# PowerDetector.net
KiCad netlist of a schematic drawn in Altium Designer
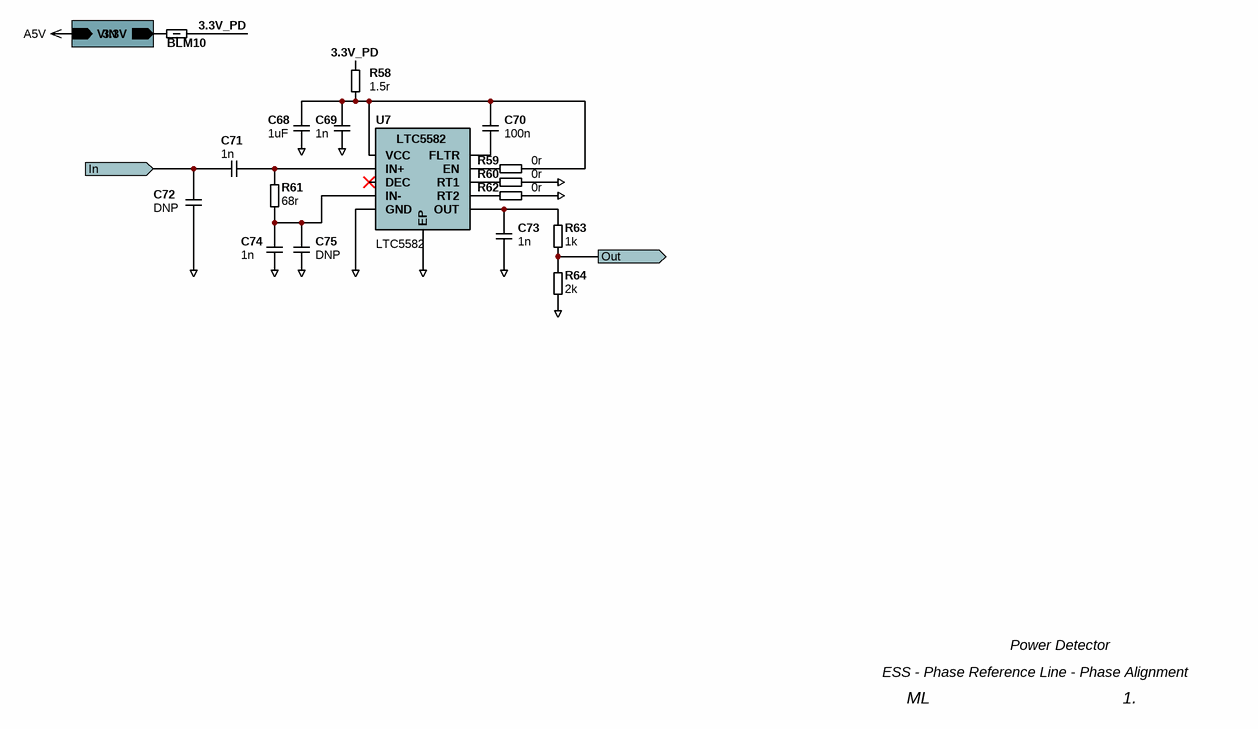
[diagram p0: PowerDetector.SchDoc]

(export (version "E")
  (design (tool "Eeschema 10.0.6"))
  (components
    (comp (ref "BLM10")
      (value "120 Ohms @ 100MHz")
      (footprint "0402-Inductor")
      (description "120 Ohms @ 100MHz 1 Power, Signal Line Ferrite Bead 0402 (1005 Metric) 700mA 130mOhm")
      (libsource (lib "PRL_PDC") (part "BLM15AX121SZ1D"))
    )
    (comp (ref "C68")
      (value "1uF")
      (footprint "0805-Capacitor")
      (description "Capacitor 0805")
      (fields (field (name "TOLERANCE") "±20%"))
      (libsource (lib "PRL_PDC") (part "C_0805"))
    )
    (comp (ref "C69")
      (value "1n")
      (footprint "0603-Capacitor")
      (description "Capacitor 0603")
      (fields (field (name "TOLERANCE") "±20%"))
      (libsource (lib "PRL_PDC") (part "C_0603"))
    )
    (comp (ref "C70")
      (value "100n")
      (footprint "0603-Capacitor")
      (description "Capacitor 0603")
      (fields (field (name "TOLERANCE") "±20%"))
      (libsource (lib "PRL_PDC") (part "C_0603"))
    )
    (comp (ref "C71")
      (value "1n")
      (footprint "0402-Capacitor")
      (description "Capacitor 0402")
      (fields (field (name "TOLERANCE") "±20%"))
      (libsource (lib "PRL_PDC") (part "C_0402"))
    )
    (comp (ref "C72")
      (value "DNP")
      (footprint "0402-Capacitor")
      (description "Capacitor 0402")
      (fields (field (name "TOLERANCE") "±20%"))
      (libsource (lib "PRL_PDC") (part "C_0402"))
    )
    (comp (ref "C73")
      (value "1n")
      (footprint "0402-Capacitor")
      (description "Capacitor 0402")
      (fields (field (name "TOLERANCE") "±20%"))
      (libsource (lib "PRL_PDC") (part "C_0402"))
    )
    (comp (ref "C74")
      (value "1n")
      (footprint "0402-Capacitor")
      (description "Capacitor 0402")
      (fields (field (name "TOLERANCE") "±20%"))
      (libsource (lib "PRL_PDC") (part "C_0402"))
    )
    (comp (ref "C75")
      (value "DNP")
      (footprint "0402-Capacitor")
      (description "Capacitor 0402")
      (fields (field (name "TOLERANCE") "±20%"))
      (libsource (lib "PRL_PDC") (part "C_0402"))
    )
    (comp (ref "R58")
      (value "1.5r")
      (footprint "0603-RESISTOR")
      (description "Resistor 0603")
      (fields (field (name "TOLERANCE") "±1%"))
      (libsource (lib "PRL_PDC") (part "R_0603"))
    )
    (comp (ref "R59")
      (value "0r")
      (footprint "0402-RESISTOR")
      (description "Resistor 0402")
      (fields (field (name "TOLERANCE") "±1%"))
      (libsource (lib "PRL_PDC") (part "R_0402"))
    )
    (comp (ref "R60")
      (value "0r")
      (footprint "0402-RESISTOR")
      (description "Resistor 0402")
      (fields (field (name "TOLERANCE") "±1%"))
      (libsource (lib "PRL_PDC") (part "R_0402"))
    )
    (comp (ref "R61")
      (value "68r")
      (footprint "0402-RESISTOR")
      (description "Resistor 0402")
      (fields (field (name "TOLERANCE") "±1%"))
      (libsource (lib "") (part "R_0402_1"))
    )
    (comp (ref "R62")
      (value "0r")
      (footprint "0402-RESISTOR")
      (description "Resistor 0402")
      (fields (field (name "TOLERANCE") "±1%"))
      (libsource (lib "PRL_PDC") (part "R_0402"))
    )
    (comp (ref "R63")
      (value "1k")
      (footprint "0402-RESISTOR")
      (description "Resistor 0402")
      (fields (field (name "TOLERANCE") "±1%"))
      (libsource (lib "") (part "R_0402_1"))
    )
    (comp (ref "R64")
      (value "2k")
      (footprint "0402-RESISTOR")
      (description "Resistor 0402")
      (fields (field (name "TOLERANCE") "±1%"))
      (libsource (lib "") (part "R_0402_1"))
    )
    (comp (ref "U7")
      (value "LTC5582")
      (footprint "LT-DFN10")
      (description "40MHz to 10GHz RMS Power Detector with 57dB Dynamic Range")
      (libsource (lib "PRL_PDC") (part "LTC5582"))
    )
  )
  (nets
    (net (code "1") (name "/3.3V") (class "Default") (node (ref "BLM10") (pin "2") (pintype "passive")))
    (net (code "2") (name "/3.3V_PD") (class "Default")
      (node (ref "BLM10") (pin "1") (pintype "passive"))
      (node (ref "R58") (pin "2") (pinfunction "2_2") (pintype "passive"))
    )
    (net (code "3") (name "/In") (class "Default")
      (node (ref "C71") (pin "1") (pinfunction "1_1") (pintype "passive"))
      (node (ref "C72") (pin "1") (pinfunction "1_1") (pintype "passive"))
    )
    (net (code "4") (name "/Out") (class "Default")
      (node (ref "R63") (pin "2") (pinfunction "2_2") (pintype "passive"))
      (node (ref "R64") (pin "1") (pinfunction "1_1") (pintype "passive"))
    )
    (net (code "6") (name "GND") (class "Default")
      (node (ref "C68") (pin "2") (pinfunction "2_2") (pintype "passive"))
      (node (ref "C69") (pin "2") (pinfunction "2_2") (pintype "passive"))
      (node (ref "C72") (pin "2") (pinfunction "2_2") (pintype "passive"))
      (node (ref "C73") (pin "2") (pinfunction "2_2") (pintype "passive"))
      (node (ref "C74") (pin "2") (pinfunction "2_2") (pintype "passive"))
      (node (ref "C75") (pin "2") (pinfunction "2_2") (pintype "passive"))
      (node (ref "R60") (pin "1") (pinfunction "1_1") (pintype "passive"))
      (node (ref "R62") (pin "1") (pinfunction "1_1") (pintype "passive"))
      (node (ref "R64") (pin "2") (pinfunction "2_2") (pintype "passive"))
      (node (ref "U7") (pin "11") (pinfunction "EP_11") (pintype "passive"))
      (node (ref "U7") (pin "5") (pinfunction "GND_5") (pintype "passive"))
    )
    (net (code "7") (name "Net-(U7-EN)") (class "Default")
      (node (ref "R59") (pin "2") (pinfunction "2_2") (pintype "passive"))
      (node (ref "U7") (pin "9") (pinfunction "EN_9") (pintype "passive"))
    )
    (net (code "8") (name "Net-(U7-FLTR)") (class "Default")
      (node (ref "C70") (pin "2") (pinfunction "2_2") (pintype "passive"))
      (node (ref "U7") (pin "10") (pinfunction "FLTR_10") (pintype "passive"))
    )
    (net (code "9") (name "Net-(U7-IN+)") (class "Default")
      (node (ref "C71") (pin "2") (pinfunction "2_2") (pintype "passive"))
      (node (ref "R61") (pin "1") (pinfunction "1_1") (pintype "passive"))
      (node (ref "U7") (pin "2") (pinfunction "IN+_2") (pintype "passive"))
    )
    (net (code "10") (name "Net-(U7-IN-)") (class "Default")
      (node (ref "C74") (pin "1") (pinfunction "1_1") (pintype "passive"))
      (node (ref "C75") (pin "1") (pinfunction "1_1") (pintype "passive"))
      (node (ref "R61") (pin "2") (pinfunction "2_2") (pintype "passive"))
      (node (ref "U7") (pin "4") (pinfunction "IN-_4") (pintype "passive"))
    )
    (net (code "11") (name "Net-(U7-OUT)") (class "Default")
      (node (ref "C73") (pin "1") (pinfunction "1_1") (pintype "passive"))
      (node (ref "R63") (pin "1") (pinfunction "1_1") (pintype "passive"))
      (node (ref "U7") (pin "6") (pinfunction "OUT_6") (pintype "passive"))
    )
    (net (code "12") (name "Net-(U7-RT1)") (class "Default")
      (node (ref "R60") (pin "2") (pinfunction "2_2") (pintype "passive"))
      (node (ref "U7") (pin "8") (pinfunction "RT1_8") (pintype "passive"))
    )
    (net (code "13") (name "Net-(U7-RT2)") (class "Default")
      (node (ref "R62") (pin "2") (pinfunction "2_2") (pintype "passive"))
      (node (ref "U7") (pin "7") (pinfunction "RT2_7") (pintype "passive"))
    )
    (net (code "14") (name "Net-(U7-VCC)") (class "Default")
      (node (ref "C68") (pin "1") (pinfunction "1_1") (pintype "passive"))
      (node (ref "C69") (pin "1") (pinfunction "1_1") (pintype "passive"))
      (node (ref "C70") (pin "1") (pinfunction "1_1") (pintype "passive"))
      (node (ref "R58") (pin "1") (pinfunction "1_1") (pintype "passive"))
      (node (ref "R59") (pin "1") (pinfunction "1_1") (pintype "passive"))
      (node (ref "U7") (pin "1") (pinfunction "VCC_1") (pintype "passive"))
    )
    (net (code "15") (name "unconnected-(U7-DEC-Pad3)") (class "Default")
      (node (ref "U7") (pin "3") (pinfunction "DEC_3") (pintype "passive+no_connect"))
    )
  )
)
